# SCH_Embedded_Watch_2023-10-27.net
KiCad netlist of a schematic drawn in EasyEDA
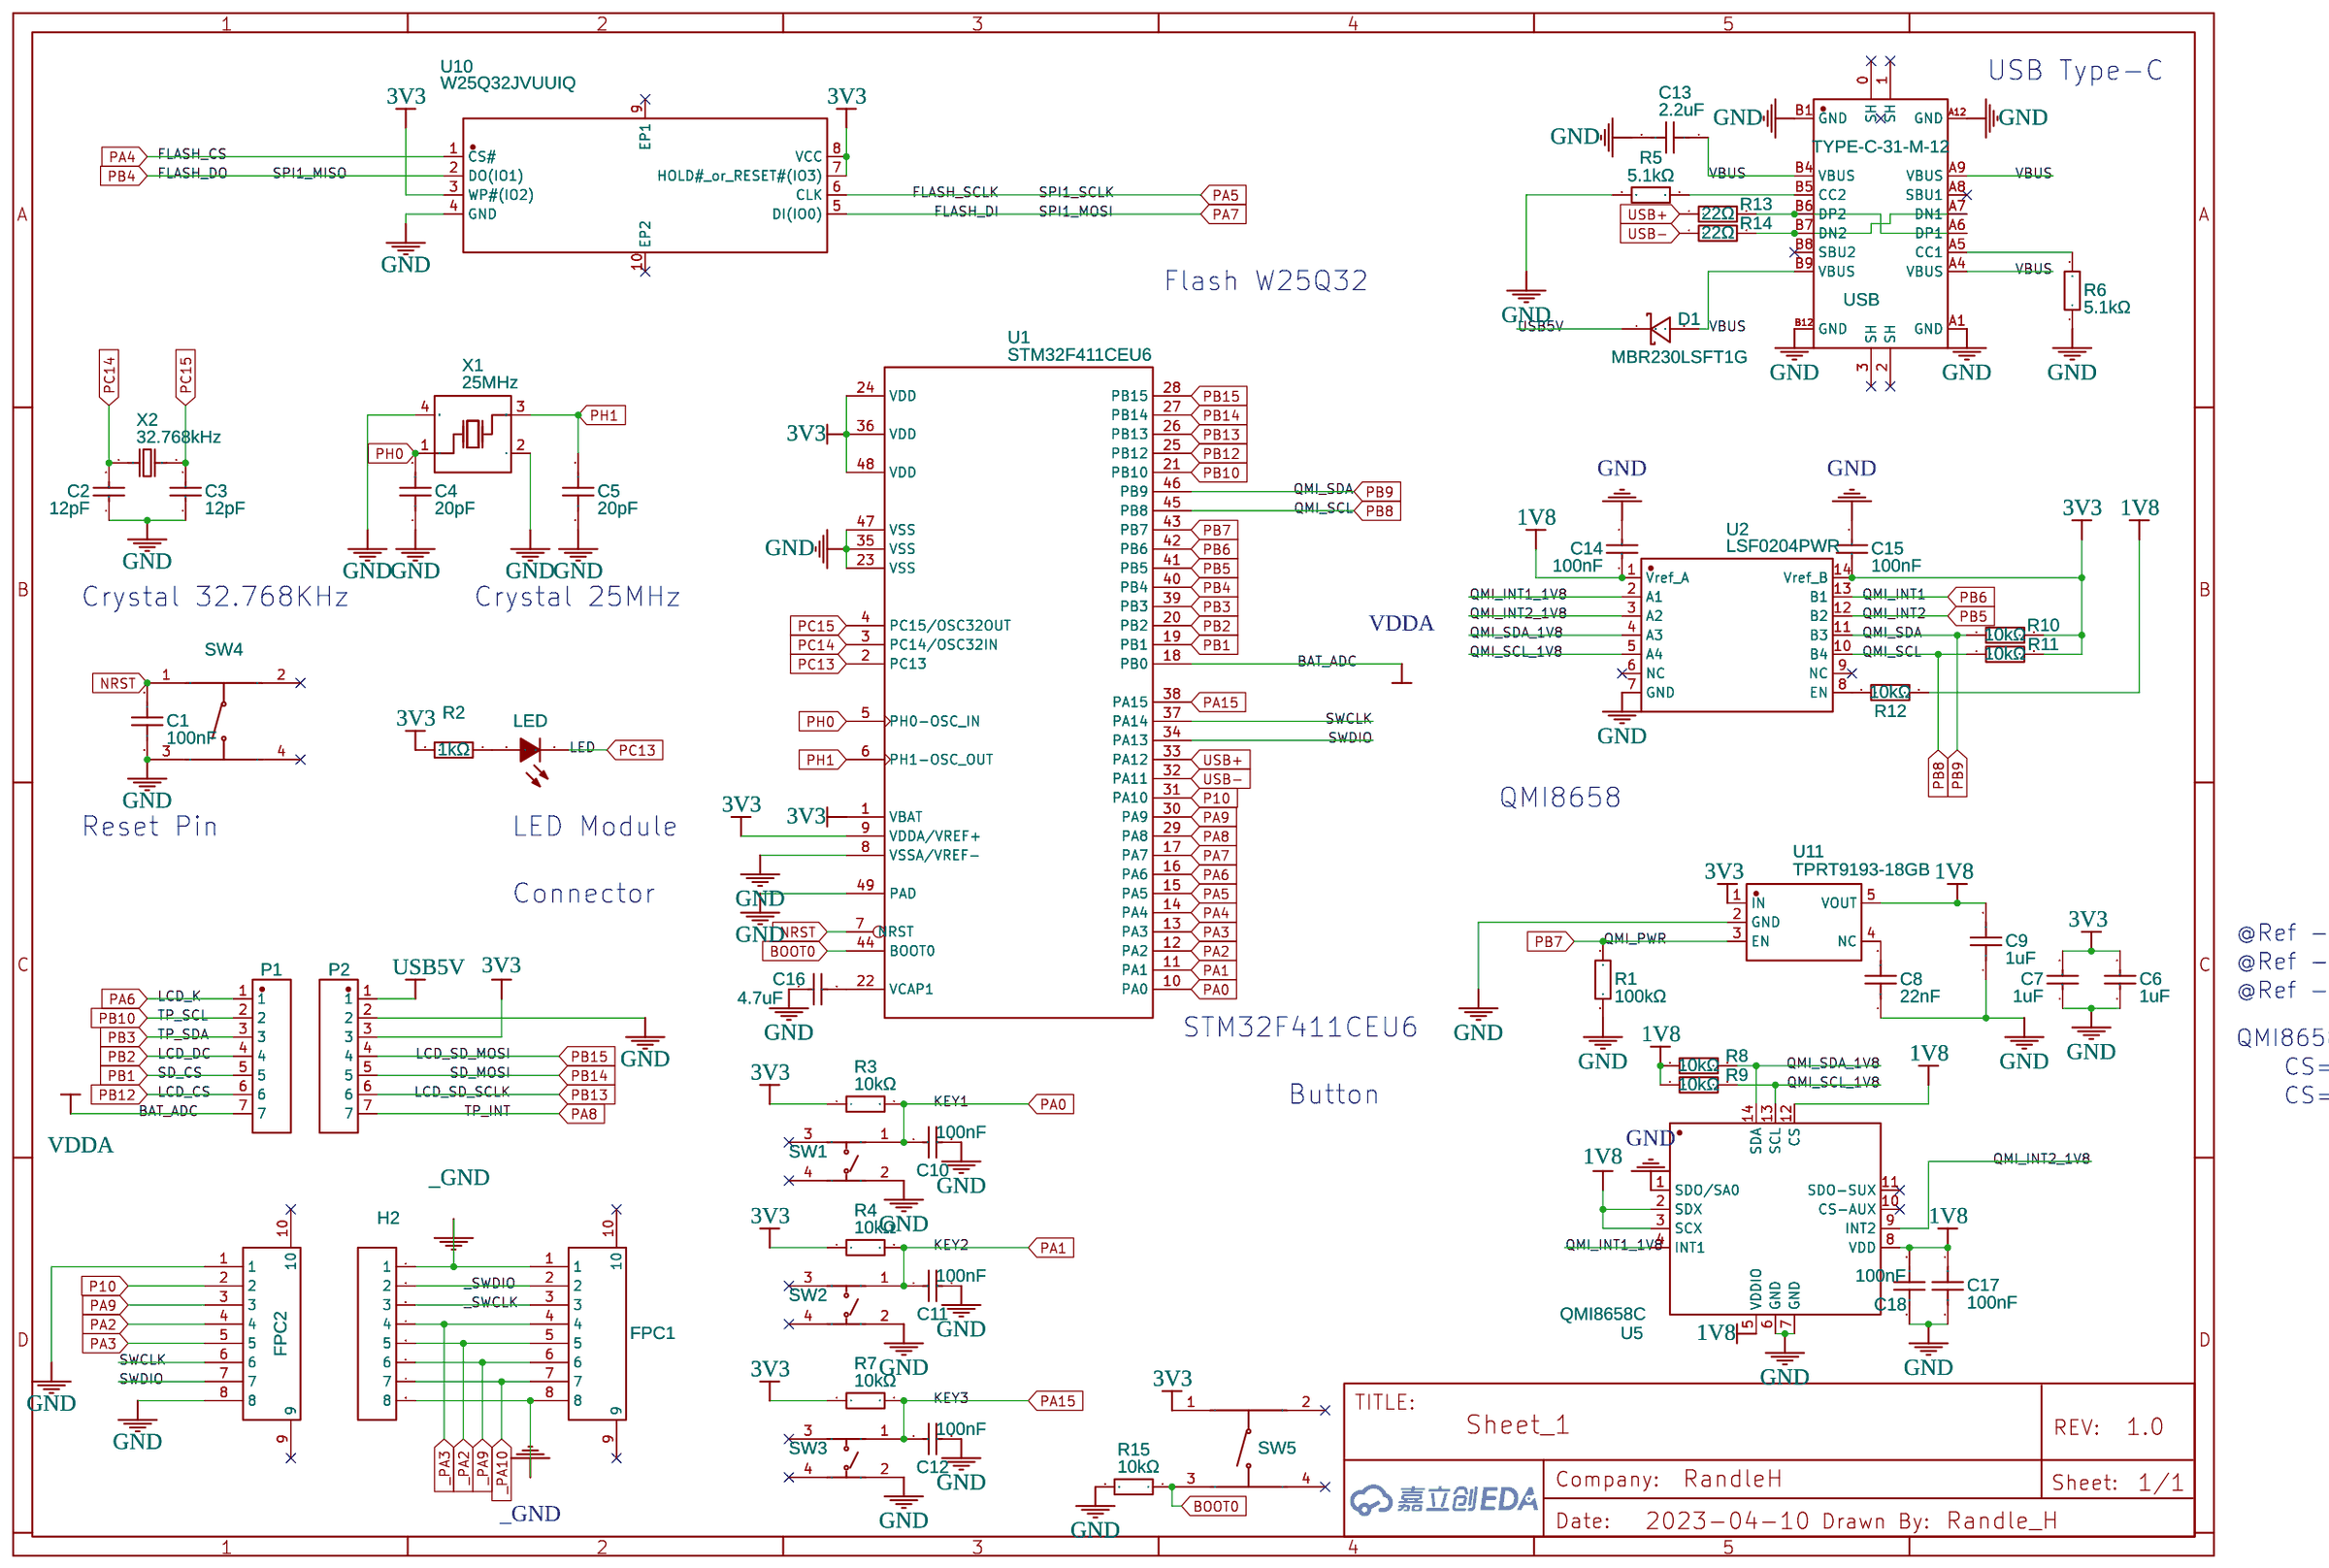
[diagram p0: schematic sheet]

(export (version "E")
  (design (tool "Eeschema 10.0.6"))
  (components
    (comp (ref "C1")
      (value "100nF")
      (fields
        (field (name "Manufacturer Part") "CL05B104KB54PNC")
        (field (name "Manufacturer") "SAMSUNG(三星)")
      )
      (libsource (lib "") (part "CL05B104KB54PNC"))
    )
    (comp (ref "C2")
      (value "12pF")
      (fields
        (field (name "Manufacturer Part") "GRM0335C1H120GA01D")
        (field (name "Manufacturer") "muRata(村田)")
      )
      (libsource (lib "") (part "GRM0335C1H120GA01D"))
    )
    (comp (ref "C3")
      (value "12pF")
      (fields
        (field (name "Manufacturer Part") "GRM0335C1H120GA01D")
        (field (name "Manufacturer") "muRata(村田)")
      )
      (libsource (lib "") (part "GRM0335C1H120GA01D_1"))
    )
    (comp (ref "C4")
      (value "20pF")
      (fields
        (field (name "Manufacturer Part") "GRM0335C1H200GA01D")
        (field (name "Manufacturer") "muRata(村田)")
      )
      (libsource (lib "") (part "GRM0335C1H200GA01D"))
    )
    (comp (ref "C5")
      (value "20pF")
      (fields
        (field (name "Manufacturer Part") "GRM0335C1H200GA01D")
        (field (name "Manufacturer") "muRata(村田)")
      )
      (libsource (lib "") (part "GRM0335C1H200GA01D"))
    )
    (comp (ref "C6")
      (value "1uF")
      (fields
        (field (name "Manufacturer Part") "GRM033R61A105ME44D")
        (field (name "Manufacturer") "muRata(村田)")
      )
      (libsource (lib "") (part "GRM033R61A105ME44D"))
    )
    (comp (ref "C7")
      (value "1uF")
      (fields
        (field (name "Manufacturer Part") "GRM033R61A105ME44D")
        (field (name "Manufacturer") "muRata(村田)")
      )
      (libsource (lib "") (part "GRM033R61A105ME44D_1"))
    )
    (comp (ref "C8")
      (value "22nF")
      (fields (field (name "Manufacturer Part") "0201X223K160NT") (field (name "Manufacturer") "FH(风华)"))
      (libsource (lib "") (part "0201X223K160NT"))
    )
    (comp (ref "C9")
      (value "1uF")
      (fields
        (field (name "Manufacturer Part") "JMK063ABJ105MP-F")
        (field (name "Manufacturer") "TAIYO YUDEN(太诱)")
      )
      (libsource (lib "") (part "JMK063ABJ105MP-F"))
    )
    (comp (ref "C10")
      (value "100nF")
      (fields
        (field (name "Manufacturer Part") "CL05B104KO5NNNC")
        (field (name "Manufacturer") "SAMSUNG(三星)")
      )
      (libsource (lib "") (part "CL05B104KO5NNNC"))
    )
    (comp (ref "C11")
      (value "100nF")
      (fields
        (field (name "Manufacturer Part") "CL05B104KO5NNNC")
        (field (name "Manufacturer") "SAMSUNG(三星)")
      )
      (libsource (lib "") (part "CL05B104KO5NNNC"))
    )
    (comp (ref "C12")
      (value "100nF")
      (fields
        (field (name "Manufacturer Part") "CL05B104KO5NNNC")
        (field (name "Manufacturer") "SAMSUNG(三星)")
      )
      (libsource (lib "") (part "CL05B104KO5NNNC"))
    )
    (comp (ref "C13")
      (value "2.2uF")
      (fields
        (field (name "Manufacturer Part") "CL21A225KBQNNNE")
        (field (name "Manufacturer") "SAMSUNG(三星)")
      )
      (libsource (lib "") (part "CL21A225KBQNNNE"))
    )
    (comp (ref "C14")
      (value "100nF")
      (fields
        (field (name "Manufacturer Part") "CL05B104KO5NNNC")
        (field (name "Manufacturer") "SAMSUNG(三星)")
      )
      (libsource (lib "") (part "CL05B104KO5NNNC_1"))
    )
    (comp (ref "C15")
      (value "100nF")
      (fields
        (field (name "Manufacturer Part") "CL05B104KO5NNNC")
        (field (name "Manufacturer") "SAMSUNG(三星)")
      )
      (libsource (lib "") (part "CL05B104KO5NNNC_2"))
    )
    (comp (ref "C16")
      (value "4.7uF")
      (fields
        (field (name "Manufacturer Part") "CL05A475MP5NRNC")
        (field (name "Manufacturer") "SAMSUNG(三星)")
      )
      (libsource (lib "") (part "CL05A475MP5NRNC"))
    )
    (comp (ref "C17")
      (value "100nF")
      (fields
        (field (name "Manufacturer Part") "CL03A104KQ3NNNC")
        (field (name "Manufacturer") "SAMSUNG(三星)")
      )
      (libsource (lib "") (part "CL03A104KQ3NNNC"))
    )
    (comp (ref "C18")
      (value "100nF")
      (fields
        (field (name "Manufacturer Part") "CL03A104KQ3NNNC")
        (field (name "Manufacturer") "SAMSUNG(三星)")
      )
      (libsource (lib "") (part "CL03A104KQ3NNNC"))
    )
    (comp (ref "D1")
      (value "MBR230LSFT1G")
      (fields (field (name "Manufacturer") "onsemi(安森美)"))
      (libsource (lib "") (part "MBR230LSFT1G"))
    )
    (comp (ref "FPC1")
      (value "AFC01-S08FCA-00")
      (fields (field (name "Manufacturer") "JS(钜硕电子)"))
      (libsource (lib "") (part "AFC01-S08FCA-00"))
    )
    (comp (ref "FPC2")
      (value "AFC01-S08FCA-00")
      (fields (field (name "Manufacturer") "JS(钜硕电子)"))
      (libsource (lib "") (part "AFC01-S08FCA-00"))
    )
    (comp (ref "H2") (value "HDR-F-2.54_1x8") (libsource (lib "") (part "HDR-F-2.54_1x8")))
    (comp (ref "LED")
      (value "19-213/Y2C-CQ2R2L/3T(CY)")
      (fields (field (name "Manufacturer") "EVERLIGHT(亿光)"))
      (libsource (lib "") (part "19-213/Y2C-CQ2R2L/3T(CY)"))
    )
    (comp (ref "P1")
      (value "PM2.54-1*7")
      (fields
        (field (name "Manufacturer Part") "X6511WVS-07H-C60D48R1")
        (field (name "Manufacturer") "XKB Connectivity(中国星坤)")
      )
      (libsource (lib "") (part "PM2.54-1*7"))
    )
    (comp (ref "P2")
      (value "PM2.54-1*7")
      (fields
        (field (name "Manufacturer Part") "X6511WVS-07H-C60D48R1")
        (field (name "Manufacturer") "XKB Connectivity(中国星坤)")
      )
      (libsource (lib "") (part "PM2.54-1*7_1"))
    )
    (comp (ref "R1")
      (value "100kΩ")
      (fields
        (field (name "Manufacturer Part") "0402WGF1003TCE")
        (field (name "Manufacturer") "UNI-ROYAL(厚声)")
      )
      (libsource (lib "") (part "0402WGF1003TCE"))
    )
    (comp (ref "R2")
      (value "1kΩ")
      (fields
        (field (name "Manufacturer Part") "0402WGF1001TCE")
        (field (name "Manufacturer") "UNI-ROYAL(厚声)")
      )
      (libsource (lib "") (part "0402WGF1001TCE"))
    )
    (comp (ref "R3")
      (value "10kΩ")
      (fields
        (field (name "Manufacturer Part") "0402WGF1002TCE")
        (field (name "Manufacturer") "UNI-ROYAL(厚声)")
      )
      (libsource (lib "") (part "0402WGF1002TCE"))
    )
    (comp (ref "R4")
      (value "10kΩ")
      (fields
        (field (name "Manufacturer Part") "0402WGF1002TCE")
        (field (name "Manufacturer") "UNI-ROYAL(厚声)")
      )
      (libsource (lib "") (part "0402WGF1002TCE"))
    )
    (comp (ref "R5")
      (value "5.1kΩ")
      (fields
        (field (name "Manufacturer Part") "0402WGF5101TCE")
        (field (name "Manufacturer") "UNI-ROYAL(厚声)")
      )
      (libsource (lib "") (part "0402WGF5101TCE_1"))
    )
    (comp (ref "R6")
      (value "5.1kΩ")
      (fields
        (field (name "Manufacturer Part") "0402WGF5101TCE")
        (field (name "Manufacturer") "UNI-ROYAL(厚声)")
      )
      (libsource (lib "") (part "0402WGF5101TCE"))
    )
    (comp (ref "R7")
      (value "10kΩ")
      (fields
        (field (name "Manufacturer Part") "0402WGF1002TCE")
        (field (name "Manufacturer") "UNI-ROYAL(厚声)")
      )
      (libsource (lib "") (part "0402WGF1002TCE"))
    )
    (comp (ref "R8")
      (value "10kΩ")
      (fields (field (name "Manufacturer Part") "RC0201JR-0710KL") (field (name "Manufacturer") "YAGEO(国巨)"))
      (libsource (lib "") (part "RC0201JR-0710KL"))
    )
    (comp (ref "R9")
      (value "10kΩ")
      (fields (field (name "Manufacturer Part") "RC0201JR-0710KL") (field (name "Manufacturer") "YAGEO(国巨)"))
      (libsource (lib "") (part "RC0201JR-0710KL"))
    )
    (comp (ref "R10")
      (value "10kΩ")
      (fields
        (field (name "Manufacturer Part") "0402WGF1002TCE")
        (field (name "Manufacturer") "UNI-ROYAL(厚声)")
      )
      (libsource (lib "") (part "0402WGF1002TCE"))
    )
    (comp (ref "R11")
      (value "10kΩ")
      (fields
        (field (name "Manufacturer Part") "0402WGF1002TCE")
        (field (name "Manufacturer") "UNI-ROYAL(厚声)")
      )
      (libsource (lib "") (part "0402WGF1002TCE"))
    )
    (comp (ref "R12")
      (value "10kΩ")
      (fields
        (field (name "Manufacturer Part") "0402WGF1002TCE")
        (field (name "Manufacturer") "UNI-ROYAL(厚声)")
      )
      (libsource (lib "") (part "0402WGF1002TCE"))
    )
    (comp (ref "R13")
      (value "22Ω")
      (fields
        (field (name "Manufacturer Part") "0402WGF220JTCE")
        (field (name "Manufacturer") "UNI-ROYAL(厚声)")
      )
      (libsource (lib "") (part "0402WGF220JTCE"))
    )
    (comp (ref "R14")
      (value "22Ω")
      (fields
        (field (name "Manufacturer Part") "0402WGF220JTCE")
        (field (name "Manufacturer") "UNI-ROYAL(厚声)")
      )
      (libsource (lib "") (part "0402WGF220JTCE"))
    )
    (comp (ref "R15")
      (value "10kΩ")
      (fields
        (field (name "Manufacturer Part") "0402WGF1002TCE")
        (field (name "Manufacturer") "UNI-ROYAL(厚声)")
      )
      (libsource (lib "") (part "0402WGF1002TCE_1"))
    )
    (comp (ref "SW1")
      (value "EVQPUD02K")
      (fields (field (name "Manufacturer") "PANASONIC(松下)"))
      (libsource (lib "") (part "EVQPUD02K"))
    )
    (comp (ref "SW2")
      (value "EVQPUD02K")
      (fields (field (name "Manufacturer") "PANASONIC(松下)"))
      (libsource (lib "") (part "EVQPUD02K"))
    )
    (comp (ref "SW3")
      (value "EVQPUD02K")
      (fields (field (name "Manufacturer") "PANASONIC(松下)"))
      (libsource (lib "") (part "EVQPUD02K"))
    )
    (comp (ref "SW4")
      (value "PTS830GM140SMTRLFS")
      (fields (field (name "Manufacturer") "C&K"))
      (libsource (lib "") (part "PTS830GM140SMTRLFS"))
    )
    (comp (ref "SW5")
      (value "PTS830GM140SMTRLFS")
      (fields (field (name "Manufacturer") "C&K"))
      (libsource (lib "") (part "PTS830GM140SMTRLFS"))
    )
    (comp (ref "U1")
      (value "STM32F411CEU6")
      (fields (field (name "Manufacturer") "ST(意法半导体)"))
      (libsource (lib "") (part "STM32F411CEU6"))
    )
    (comp (ref "U2")
      (value "LSF0204PWR")
      (fields (field (name "Manufacturer") "TI(德州仪器)"))
      (libsource (lib "") (part "LSF0204PWR"))
    )
    (comp (ref "U5")
      (value "QMI8658C")
      (fields (field (name "Manufacturer") "QST(上海矽睿)"))
      (libsource (lib "") (part "QMI8658C"))
    )
    (comp (ref "U10")
      (value "W25Q32JVUUIQ")
      (fields (field (name "Manufacturer") "WINBOND(华邦)"))
      (libsource (lib "") (part "W25Q32JVUUIQ"))
    )
    (comp (ref "U11")
      (value "TPRT9193-18GB")
      (fields (field (name "Manufacturer") "TECH PUBLIC(台舟)"))
      (libsource (lib "") (part "TPRT9193-18GB"))
    )
    (comp (ref "USB")
      (value "TYPE-C-31-M-12")
      (fields (field (name "Manufacturer") "韩国韩荣"))
      (libsource (lib "") (part "TYPE-C-31-M-12"))
    )
    (comp (ref "X1")
      (value "25MHz")
      (fields (field (name "Manufacturer Part") "TAXM25M4RLBCCT2T") (field (name "Manufacturer") "TAE(雅晶鑫)"))
      (libsource (lib "") (part "SMD-3225_4P25MHZ20PF10PPM-40&#126;+85℃"))
    )
    (comp (ref "X2")
      (value "32.768kHz")
      (fields (field (name "Manufacturer Part") "Q13FC1350000400") (field (name "Manufacturer") "EPSON(爱普生)"))
      (libsource (lib "") (part "Q13FC1350000400"))
    )
  )
  (nets
    (net (code "1") (name "/QMI_INT1_1V8") (class "Default")
      (node (ref "U2") (pin "2") (pinfunction "A1_2") (pintype "unspecified"))
      (node (ref "U5") (pin "4") (pinfunction "INT1_4") (pintype "unspecified"))
    )
    (net (code "2") (name "/QMI_INT2_1V8") (class "Default")
      (node (ref "U2") (pin "3") (pinfunction "A2_3") (pintype "unspecified"))
      (node (ref "U5") (pin "9") (pinfunction "INT2_9") (pintype "unspecified"))
    )
    (net (code "3") (name "/QMI_SCL_1V8") (class "Default")
      (node (ref "R9") (pin "2") (pinfunction "2_2") (pintype "input"))
      (node (ref "U2") (pin "5") (pinfunction "A4_5") (pintype "unspecified"))
      (node (ref "U5") (pin "13") (pinfunction "SCL_13") (pintype "unspecified"))
    )
    (net (code "4") (name "/QMI_SDA_1V8") (class "Default")
      (node (ref "R8") (pin "2") (pinfunction "2_2") (pintype "input"))
      (node (ref "U2") (pin "4") (pinfunction "A3_4") (pintype "unspecified"))
      (node (ref "U5") (pin "14") (pinfunction "SDA_14") (pintype "unspecified"))
    )
    (net (code "5") (name "/SWCLK") (class "Default")
      (node (ref "FPC2") (pin "6") (pinfunction "6_6") (pintype "unspecified"))
      (node (ref "U1") (pin "37") (pinfunction "PA14_37") (pintype "unspecified"))
    )
    (net (code "6") (name "/SWDIO") (class "Default")
      (node (ref "FPC2") (pin "7") (pinfunction "7_7") (pintype "unspecified"))
      (node (ref "U1") (pin "34") (pinfunction "PA13_34") (pintype "unspecified"))
    )
    (net (code "7") (name "/VBUS") (class "Default")
      (node (ref "C13") (pin "1") (pinfunction "1_1") (pintype "unspecified"))
      (node (ref "D1") (pin "2") (pinfunction "A_2") (pintype "unspecified"))
      (node (ref "USB") (pin "A4") (pinfunction "VBUS_A4") (pintype "unspecified"))
      (node (ref "USB") (pin "A9") (pinfunction "VBUS_A9") (pintype "unspecified"))
      (node (ref "USB") (pin "B4") (pinfunction "VBUS_B4") (pintype "unspecified"))
      (node (ref "USB") (pin "B9") (pinfunction "VBUS_B9") (pintype "unspecified"))
    )
    (net (code "8") (name "/_SWCLK") (class "Default")
      (node (ref "FPC1") (pin "3") (pinfunction "3_3") (pintype "unspecified"))
      (node (ref "H2") (pin "3") (pinfunction "3_3") (pintype "unspecified"))
    )
    (net (code "9") (name "/_SWDIO") (class "Default")
      (node (ref "FPC1") (pin "2") (pinfunction "2_2") (pintype "unspecified"))
      (node (ref "H2") (pin "2") (pinfunction "2_2") (pintype "unspecified"))
    )
    (net (code "10") (name "1V8") (class "Default")
      (node (ref "C14") (pin "1") (pinfunction "1_1") (pintype "input"))
      (node (ref "C17") (pin "1") (pinfunction "1_1") (pintype "unspecified"))
      (node (ref "C18") (pin "1") (pinfunction "1_1") (pintype "unspecified"))
      (node (ref "C9") (pin "2") (pinfunction "2_2") (pintype "unspecified"))
      (node (ref "R12") (pin "2") (pinfunction "2_2") (pintype "input"))
      (node (ref "R8") (pin "1") (pinfunction "1_1") (pintype "input"))
      (node (ref "R9") (pin "1") (pinfunction "1_1") (pintype "input"))
      (node (ref "U11") (pin "5") (pinfunction "VOUT_5") (pintype "unspecified"))
      (node (ref "U2") (pin "1") (pinfunction "Vref_A_1") (pintype "unspecified"))
      (node (ref "U5") (pin "12") (pinfunction "CS_12") (pintype "unspecified"))
      (node (ref "U5") (pin "2") (pinfunction "SDX_2") (pintype "unspecified"))
      (node (ref "U5") (pin "3") (pinfunction "SCX_3") (pintype "unspecified"))
      (node (ref "U5") (pin "5") (pinfunction "VDDIO_5") (pintype "unspecified"))
      (node (ref "U5") (pin "8") (pinfunction "VDD_8") (pintype "unspecified"))
    )
    (net (code "11") (name "3V3") (class "Default")
      (node (ref "C15") (pin "1") (pinfunction "1_1") (pintype "input"))
      (node (ref "C6") (pin "2") (pinfunction "2_2") (pintype "input"))
      (node (ref "C7") (pin "2") (pinfunction "2_2") (pintype "input"))
      (node (ref "P2") (pin "3") (pinfunction "3_3") (pintype "unspecified"))
      (node (ref "R10") (pin "2") (pinfunction "2_2") (pintype "input"))
      (node (ref "R11") (pin "2") (pinfunction "2_2") (pintype "input"))
      (node (ref "R2") (pin "1") (pinfunction "1_1") (pintype "input"))
      (node (ref "R3") (pin "1") (pinfunction "1_1") (pintype "input"))
      (node (ref "R4") (pin "1") (pinfunction "1_1") (pintype "input"))
      (node (ref "R7") (pin "1") (pinfunction "1_1") (pintype "input"))
      (node (ref "SW5") (pin "1") (pinfunction "1_1") (pintype "unspecified"))
      (node (ref "U1") (pin "1") (pinfunction "VBAT_1") (pintype "passive"))
      (node (ref "U1") (pin "24") (pinfunction "VDD_24") (pintype "unspecified"))
      (node (ref "U1") (pin "36") (pinfunction "VDD_36") (pintype "unspecified"))
      (node (ref "U1") (pin "48") (pinfunction "VDD_48") (pintype "unspecified"))
      (node (ref "U1") (pin "9") (pinfunction "VDDA/VREF+_9") (pintype "passive"))
      (node (ref "U10") (pin "3") (pinfunction "WP#(IO2)_3") (pintype "unspecified"))
      (node (ref "U10") (pin "7") (pinfunction "HOLD#_or_RESET#(IO3)_7") (pintype "unspecified"))
      (node (ref "U10") (pin "8") (pinfunction "VCC_8") (pintype "unspecified"))
      (node (ref "U11") (pin "1") (pinfunction "IN_1") (pintype "unspecified"))
      (node (ref "U2") (pin "14") (pinfunction "Vref_B_14") (pintype "unspecified"))
    )
    (net (code "12") (name "BOOT0") (class "Default")
      (node (ref "R15") (pin "1") (pinfunction "1_1") (pintype "input"))
      (node (ref "SW5") (pin "3") (pinfunction "3_3") (pintype "unspecified"))
      (node (ref "U1") (pin "44") (pinfunction "BOOT0_44") (pintype "input"))
    )
    (net (code "13") (name "GND") (class "Default")
      (node (ref "C1") (pin "1") (pinfunction "1_1") (pintype "unspecified"))
      (node (ref "C10") (pin "2") (pinfunction "2_2") (pintype "input"))
      (node (ref "C11") (pin "2") (pinfunction "2_2") (pintype "input"))
      (node (ref "C12") (pin "2") (pinfunction "2_2") (pintype "input"))
      (node (ref "C13") (pin "2") (pinfunction "2_2") (pintype "unspecified"))
      (node (ref "C14") (pin "2") (pinfunction "2_2") (pintype "input"))
      (node (ref "C15") (pin "2") (pinfunction "2_2") (pintype "input"))
      (node (ref "C16") (pin "1") (pinfunction "1_1") (pintype "input"))
      (node (ref "C17") (pin "2") (pinfunction "2_2") (pintype "unspecified"))
      (node (ref "C18") (pin "2") (pinfunction "2_2") (pintype "unspecified"))
      (node (ref "C2") (pin "1") (pinfunction "1_1") (pintype "input"))
      (node (ref "C3") (pin "1") (pinfunction "1_1") (pintype "input"))
      (node (ref "C4") (pin "1") (pinfunction "1_1") (pintype "unspecified"))
      (node (ref "C5") (pin "1") (pinfunction "1_1") (pintype "unspecified"))
      (node (ref "C6") (pin "1") (pinfunction "1_1") (pintype "input"))
      (node (ref "C7") (pin "1") (pinfunction "1_1") (pintype "input"))
      (node (ref "C8") (pin "1") (pinfunction "1_1") (pintype "unspecified"))
      (node (ref "C9") (pin "1") (pinfunction "1_1") (pintype "unspecified"))
      (node (ref "FPC2") (pin "1") (pinfunction "1_1") (pintype "unspecified"))
      (node (ref "FPC2") (pin "8") (pinfunction "8_8") (pintype "unspecified"))
      (node (ref "P2") (pin "2") (pinfunction "2_2") (pintype "unspecified"))
      (node (ref "R1") (pin "1") (pinfunction "1_1") (pintype "input"))
      (node (ref "R15") (pin "2") (pinfunction "2_2") (pintype "input"))
      (node (ref "R5") (pin "2") (pinfunction "2_2") (pintype "input"))
      (node (ref "R6") (pin "1") (pinfunction "1_1") (pintype "input"))
      (node (ref "SW1") (pin "2") (pinfunction "2_2") (pintype "unspecified"))
      (node (ref "SW2") (pin "2") (pinfunction "2_2") (pintype "unspecified"))
      (node (ref "SW3") (pin "2") (pinfunction "2_2") (pintype "unspecified"))
      (node (ref "SW4") (pin "3") (pinfunction "3_3") (pintype "unspecified"))
      (node (ref "U1") (pin "23") (pinfunction "VSS_23") (pintype "unspecified"))
      (node (ref "U1") (pin "35") (pinfunction "VSS_35") (pintype "unspecified"))
      (node (ref "U1") (pin "47") (pinfunction "VSS_47") (pintype "unspecified"))
      (node (ref "U1") (pin "49") (pinfunction "PAD_49") (pintype "passive"))
      (node (ref "U1") (pin "8") (pinfunction "VSSA/VREF-_8") (pintype "passive"))
      (node (ref "U10") (pin "4") (pinfunction "GND_4") (pintype "unspecified"))
      (node (ref "U11") (pin "2") (pinfunction "GND_2") (pintype "unspecified"))
      (node (ref "U2") (pin "7") (pinfunction "GND_7") (pintype "unspecified"))
      (node (ref "U5") (pin "1") (pinfunction "SDO/SA0_1") (pintype "unspecified"))
      (node (ref "U5") (pin "6") (pinfunction "GND_6") (pintype "unspecified"))
      (node (ref "U5") (pin "7") (pinfunction "GND_7") (pintype "unspecified"))
      (node (ref "USB") (pin "A1") (pinfunction "GND_A1") (pintype "unspecified"))
      (node (ref "USB") (pin "A12") (pinfunction "GND_A12") (pintype "unspecified"))
      (node (ref "USB") (pin "B1") (pinfunction "GND_B1") (pintype "unspecified"))
      (node (ref "USB") (pin "B12") (pinfunction "GND_B12") (pintype "unspecified"))
      (node (ref "X1") (pin "2") (pinfunction "GND_2") (pintype "unspecified"))
      (node (ref "X1") (pin "4") (pinfunction "GND_4") (pintype "unspecified"))
    )
    (net (code "14") (name "NRST") (class "Default")
      (node (ref "C1") (pin "2") (pinfunction "2_2") (pintype "unspecified"))
      (node (ref "SW4") (pin "1") (pinfunction "1_1") (pintype "unspecified"))
      (node (ref "U1") (pin "7") (pinfunction "NRST_7") (pintype "unspecified"))
    )
    (net (code "15") (name "Net-(LED-A)") (class "Default")
      (node (ref "LED") (pin "2") (pinfunction "A_2") (pintype "input"))
      (node (ref "R2") (pin "2") (pinfunction "2_2") (pintype "input"))
    )
    (net (code "16") (name "Net-(U1-VCAP1)") (class "Default")
      (node (ref "C16") (pin "2") (pinfunction "2_2") (pintype "input"))
      (node (ref "U1") (pin "22") (pinfunction "VCAP1_22") (pintype "passive"))
    )
    (net (code "17") (name "Net-(U2-EN)") (class "Default")
      (node (ref "R12") (pin "1") (pinfunction "1_1") (pintype "input"))
      (node (ref "U2") (pin "8") (pinfunction "EN_8") (pintype "unspecified"))
    )
    (net (code "18") (name "Net-(U11-NC)") (class "Default")
      (node (ref "C8") (pin "2") (pinfunction "2_2") (pintype "unspecified"))
      (node (ref "U11") (pin "4") (pinfunction "NC_4") (pintype "unspecified"))
    )
    (net (code "19") (name "Net-(USB-CC1)") (class "Default")
      (node (ref "R6") (pin "2") (pinfunction "2_2") (pintype "input"))
      (node (ref "USB") (pin "A5") (pinfunction "CC1_A5") (pintype "unspecified"))
    )
    (net (code "20") (name "Net-(USB-CC2)") (class "Default")
      (node (ref "R5") (pin "1") (pinfunction "1_1") (pintype "input"))
      (node (ref "USB") (pin "B5") (pinfunction "CC2_B5") (pintype "unspecified"))
    )
    (net (code "21") (name "Net-(USB-DN1)") (class "Default")
      (node (ref "R14") (pin "2") (pinfunction "2_2") (pintype "input"))
      (node (ref "USB") (pin "A7") (pinfunction "DN1_A7") (pintype "unspecified"))
      (node (ref "USB") (pin "B7") (pinfunction "DN2_B7") (pintype "unspecified"))
    )
    (net (code "22") (name "Net-(USB-DP1)") (class "Default")
      (node (ref "R13") (pin "2") (pinfunction "2_2") (pintype "input"))
      (node (ref "USB") (pin "A6") (pinfunction "DP1_A6") (pintype "unspecified"))
      (node (ref "USB") (pin "B6") (pinfunction "DP2_B6") (pintype "unspecified"))
    )
    (net (code "23") (name "P10") (class "Default")
      (node (ref "FPC2") (pin "2") (pinfunction "2_2") (pintype "unspecified"))
      (node (ref "U1") (pin "31") (pinfunction "PA10_31") (pintype "unspecified"))
    )
    (net (code "24") (name "PA0") (class "Default")
      (node (ref "C10") (pin "1") (pinfunction "1_1") (pintype "input"))
      (node (ref "R3") (pin "2") (pinfunction "2_2") (pintype "input"))
      (node (ref "SW1") (pin "1") (pinfunction "1_1") (pintype "unspecified"))
      (node (ref "U1") (pin "10") (pinfunction "PA0_10") (pintype "unspecified"))
    )
    (net (code "25") (name "PA1") (class "Default")
      (node (ref "C11") (pin "1") (pinfunction "1_1") (pintype "input"))
      (node (ref "R4") (pin "2") (pinfunction "2_2") (pintype "input"))
      (node (ref "SW2") (pin "1") (pinfunction "1_1") (pintype "unspecified"))
      (node (ref "U1") (pin "11") (pinfunction "PA1_11") (pintype "unspecified"))
    )
    (net (code "26") (name "PA2") (class "Default")
      (node (ref "FPC2") (pin "4") (pinfunction "4_4") (pintype "unspecified"))
      (node (ref "U1") (pin "12") (pinfunction "PA2_12") (pintype "unspecified"))
    )
    (net (code "27") (name "PA3") (class "Default")
      (node (ref "FPC2") (pin "5") (pinfunction "5_5") (pintype "unspecified"))
      (node (ref "U1") (pin "13") (pinfunction "PA3_13") (pintype "unspecified"))
    )
    (net (code "28") (name "PA4") (class "Default")
      (node (ref "U1") (pin "14") (pinfunction "PA4_14") (pintype "unspecified"))
      (node (ref "U10") (pin "1") (pinfunction "CS#_1") (pintype "unspecified"))
    )
    (net (code "29") (name "PA5") (class "Default")
      (node (ref "U1") (pin "15") (pinfunction "PA5_15") (pintype "unspecified"))
      (node (ref "U10") (pin "6") (pinfunction "CLK_6") (pintype "unspecified"))
    )
    (net (code "30") (name "PA6") (class "Default")
      (node (ref "P1") (pin "1") (pinfunction "1_1") (pintype "unspecified"))
      (node (ref "U1") (pin "16") (pinfunction "PA6_16") (pintype "unspecified"))
    )
    (net (code "31") (name "PA7") (class "Default")
      (node (ref "U1") (pin "17") (pinfunction "PA7_17") (pintype "unspecified"))
      (node (ref "U10") (pin "5") (pinfunction "DI(IO0)_5") (pintype "unspecified"))
    )
    (net (code "32") (name "PA8") (class "Default")
      (node (ref "P2") (pin "7") (pinfunction "7_7") (pintype "unspecified"))
      (node (ref "U1") (pin "29") (pinfunction "PA8_29") (pintype "unspecified"))
    )
    (net (code "33") (name "PA9") (class "Default")
      (node (ref "FPC2") (pin "3") (pinfunction "3_3") (pintype "unspecified"))
      (node (ref "U1") (pin "30") (pinfunction "PA9_30") (pintype "unspecified"))
    )
    (net (code "34") (name "PA15") (class "Default")
      (node (ref "C12") (pin "1") (pinfunction "1_1") (pintype "input"))
      (node (ref "R7") (pin "2") (pinfunction "2_2") (pintype "input"))
      (node (ref "SW3") (pin "1") (pinfunction "1_1") (pintype "unspecified"))
      (node (ref "U1") (pin "38") (pinfunction "PA15_38") (pintype "unspecified"))
    )
    (net (code "35") (name "PB1") (class "Default")
      (node (ref "P1") (pin "5") (pinfunction "5_5") (pintype "unspecified"))
      (node (ref "U1") (pin "19") (pinfunction "PB1_19") (pintype "unspecified"))
    )
    (net (code "36") (name "PB2") (class "Default")
      (node (ref "P1") (pin "4") (pinfunction "4_4") (pintype "unspecified"))
      (node (ref "U1") (pin "20") (pinfunction "PB2_20") (pintype "unspecified"))
    )
    (net (code "37") (name "PB3") (class "Default")
      (node (ref "P1") (pin "3") (pinfunction "3_3") (pintype "unspecified"))
      (node (ref "U1") (pin "39") (pinfunction "PB3_39") (pintype "unspecified"))
    )
    (net (code "38") (name "PB4") (class "Default")
      (node (ref "U1") (pin "40") (pinfunction "PB4_40") (pintype "unspecified"))
      (node (ref "U10") (pin "2") (pinfunction "DO(IO1)_2") (pintype "unspecified"))
    )
    (net (code "39") (name "PB5") (class "Default")
      (node (ref "U1") (pin "41") (pinfunction "PB5_41") (pintype "unspecified"))
      (node (ref "U2") (pin "12") (pinfunction "B2_12") (pintype "unspecified"))
    )
    (net (code "40") (name "PB6") (class "Default")
      (node (ref "U1") (pin "42") (pinfunction "PB6_42") (pintype "unspecified"))
      (node (ref "U2") (pin "13") (pinfunction "B1_13") (pintype "unspecified"))
    )
    (net (code "41") (name "PB7") (class "Default")
      (node (ref "R1") (pin "2") (pinfunction "2_2") (pintype "input"))
      (node (ref "U1") (pin "43") (pinfunction "PB7_43") (pintype "unspecified"))
      (node (ref "U11") (pin "3") (pinfunction "EN_3") (pintype "unspecified"))
    )
    (net (code "42") (name "PB8") (class "Default")
      (node (ref "R11") (pin "1") (pinfunction "1_1") (pintype "input"))
      (node (ref "U1") (pin "45") (pinfunction "PB8_45") (pintype "unspecified"))
      (node (ref "U2") (pin "10") (pinfunction "B4_10") (pintype "unspecified"))
    )
    (net (code "43") (name "PB9") (class "Default")
      (node (ref "R10") (pin "1") (pinfunction "1_1") (pintype "input"))
      (node (ref "U1") (pin "46") (pinfunction "PB9_46") (pintype "unspecified"))
      (node (ref "U2") (pin "11") (pinfunction "B3_11") (pintype "unspecified"))
    )
    (net (code "44") (name "PB10") (class "Default")
      (node (ref "P1") (pin "2") (pinfunction "2_2") (pintype "unspecified"))
      (node (ref "U1") (pin "21") (pinfunction "PB10_21") (pintype "unspecified"))
    )
    (net (code "45") (name "PB12") (class "Default")
      (node (ref "P1") (pin "6") (pinfunction "6_6") (pintype "unspecified"))
      (node (ref "U1") (pin "25") (pinfunction "PB12_25") (pintype "unspecified"))
    )
    (net (code "46") (name "PB13") (class "Default")
      (node (ref "P2") (pin "6") (pinfunction "6_6") (pintype "unspecified"))
      (node (ref "U1") (pin "26") (pinfunction "PB13_26") (pintype "unspecified"))
    )
    (net (code "47") (name "PB14") (class "Default")
      (node (ref "P2") (pin "5") (pinfunction "5_5") (pintype "unspecified"))
      (node (ref "U1") (pin "27") (pinfunction "PB14_27") (pintype "unspecified"))
    )
    (net (code "48") (name "PB15") (class "Default")
      (node (ref "P2") (pin "4") (pinfunction "4_4") (pintype "unspecified"))
      (node (ref "U1") (pin "28") (pinfunction "PB15_28") (pintype "unspecified"))
    )
    (net (code "49") (name "PC13") (class "Default")
      (node (ref "LED") (pin "1") (pinfunction "C_1") (pintype "input"))
      (node (ref "U1") (pin "2") (pinfunction "PC13_2") (pintype "unspecified"))
    )
    (net (code "50") (name "PC14") (class "Default")
      (node (ref "C2") (pin "2") (pinfunction "2_2") (pintype "input"))
      (node (ref "U1") (pin "3") (pinfunction "PC14/OSC32IN_3") (pintype "unspecified"))
      (node (ref "X2") (pin "1") (pinfunction "1_1") (pintype "unspecified"))
    )
    (net (code "51") (name "PC15") (class "Default")
      (node (ref "C3") (pin "2") (pinfunction "2_2") (pintype "input"))
      (node (ref "U1") (pin "4") (pinfunction "PC15/OSC32OUT_4") (pintype "unspecified"))
      (node (ref "X2") (pin "2") (pinfunction "2_2") (pintype "unspecified"))
    )
    (net (code "52") (name "PH0") (class "Default")
      (node (ref "C4") (pin "2") (pinfunction "2_2") (pintype "unspecified"))
      (node (ref "U1") (pin "5") (pinfunction "PH0-OSC_IN_5") (pintype "unspecified"))
      (node (ref "X1") (pin "1") (pinfunction "OSC1_1") (pintype "unspecified"))
    )
    (net (code "53") (name "PH1") (class "Default")
      (node (ref "C5") (pin "2") (pinfunction "2_2") (pintype "unspecified"))
      (node (ref "U1") (pin "6") (pinfunction "PH1-OSC_OUT_6") (pintype "unspecified"))
      (node (ref "X1") (pin "3") (pinfunction "OSC2_3") (pintype "unspecified"))
    )
    (net (code "54") (name "USB+") (class "Default")
      (node (ref "R13") (pin "1") (pinfunction "1_1") (pintype "input"))
      (node (ref "U1") (pin "33") (pinfunction "PA12_33") (pintype "unspecified"))
    )
    (net (code "55") (name "USB-") (class "Default")
      (node (ref "R14") (pin "1") (pinfunction "1_1") (pintype "input"))
      (node (ref "U1") (pin "32") (pinfunction "PA11_32") (pintype "unspecified"))
    )
    (net (code "56") (name "USB5V") (class "Default")
      (node (ref "D1") (pin "1") (pinfunction "C_1") (pintype "unspecified"))
      (node (ref "P2") (pin "1") (pinfunction "1_1") (pintype "unspecified"))
    )
    (net (code "57") (name "VDDA") (class "Default")
      (node (ref "P1") (pin "7") (pinfunction "7_7") (pintype "unspecified"))
      (node (ref "U1") (pin "18") (pinfunction "PB0_18") (pintype "unspecified"))
    )
    (net (code "58") (name "_GND") (class "Default")
      (node (ref "FPC1") (pin "1") (pinfunction "1_1") (pintype "unspecified"))
      (node (ref "FPC1") (pin "8") (pinfunction "8_8") (pintype "unspecified"))
      (node (ref "H2") (pin "1") (pinfunction "1_1") (pintype "unspecified"))
      (node (ref "H2") (pin "8") (pinfunction "8_8") (pintype "unspecified"))
    )
    (net (code "59") (name "_PA2") (class "Default")
      (node (ref "FPC1") (pin "5") (pinfunction "5_5") (pintype "unspecified"))
      (node (ref "H2") (pin "5") (pinfunction "5_5") (pintype "unspecified"))
    )
    (net (code "60") (name "_PA3") (class "Default")
      (node (ref "FPC1") (pin "4") (pinfunction "4_4") (pintype "unspecified"))
      (node (ref "H2") (pin "4") (pinfunction "4_4") (pintype "unspecified"))
    )
    (net (code "61") (name "_PA9") (class "Default")
      (node (ref "FPC1") (pin "6") (pinfunction "6_6") (pintype "unspecified"))
      (node (ref "H2") (pin "6") (pinfunction "6_6") (pintype "unspecified"))
    )
    (net (code "62") (name "_PA10") (class "Default")
      (node (ref "FPC1") (pin "7") (pinfunction "7_7") (pintype "unspecified"))
      (node (ref "H2") (pin "7") (pinfunction "7_7") (pintype "unspecified"))
    )
    (net (code "63") (name "unconnected-(FPC1-Pad9)") (class "Default")
      (node (ref "FPC1") (pin "9") (pinfunction "9_9") (pintype "unspecified+no_connect"))
    )
    (net (code "64") (name "unconnected-(FPC1-Pad10)") (class "Default")
      (node (ref "FPC1") (pin "10") (pinfunction "10_10") (pintype "unspecified+no_connect"))
    )
    (net (code "65") (name "unconnected-(FPC2-Pad9)") (class "Default")
      (node (ref "FPC2") (pin "9") (pinfunction "9_9") (pintype "unspecified+no_connect"))
    )
    (net (code "66") (name "unconnected-(FPC2-Pad10)") (class "Default")
      (node (ref "FPC2") (pin "10") (pinfunction "10_10") (pintype "unspecified+no_connect"))
    )
    (net (code "67") (name "unconnected-(SW1-Pad3)") (class "Default")
      (node (ref "SW1") (pin "3") (pinfunction "3_3") (pintype "unspecified+no_connect"))
    )
    (net (code "68") (name "unconnected-(SW1-Pad4)") (class "Default")
      (node (ref "SW1") (pin "4") (pinfunction "4_4") (pintype "unspecified+no_connect"))
    )
    (net (code "69") (name "unconnected-(SW2-Pad3)") (class "Default")
      (node (ref "SW2") (pin "3") (pinfunction "3_3") (pintype "unspecified+no_connect"))
    )
    (net (code "70") (name "unconnected-(SW2-Pad4)") (class "Default")
      (node (ref "SW2") (pin "4") (pinfunction "4_4") (pintype "unspecified+no_connect"))
    )
    (net (code "71") (name "unconnected-(SW3-Pad3)") (class "Default")
      (node (ref "SW3") (pin "3") (pinfunction "3_3") (pintype "unspecified+no_connect"))
    )
    (net (code "72") (name "unconnected-(SW3-Pad4)") (class "Default")
      (node (ref "SW3") (pin "4") (pinfunction "4_4") (pintype "unspecified+no_connect"))
    )
    (net (code "73") (name "unconnected-(SW4-Pad2)") (class "Default")
      (node (ref "SW4") (pin "2") (pinfunction "2_2") (pintype "unspecified+no_connect"))
    )
    (net (code "74") (name "unconnected-(SW4-Pad4)") (class "Default")
      (node (ref "SW4") (pin "4") (pinfunction "4_4") (pintype "unspecified+no_connect"))
    )
    (net (code "75") (name "unconnected-(SW5-Pad2)") (class "Default")
      (node (ref "SW5") (pin "2") (pinfunction "2_2") (pintype "unspecified+no_connect"))
    )
    (net (code "76") (name "unconnected-(SW5-Pad4)") (class "Default")
      (node (ref "SW5") (pin "4") (pinfunction "4_4") (pintype "unspecified+no_connect"))
    )
    (net (code "77") (name "unconnected-(U2-NC-Pad6)") (class "Default")
      (node (ref "U2") (pin "6") (pinfunction "NC_6") (pintype "unspecified+no_connect"))
    )
    (net (code "78") (name "unconnected-(U2-NC-Pad9)") (class "Default")
      (node (ref "U2") (pin "9") (pinfunction "NC_9") (pintype "unspecified+no_connect"))
    )
    (net (code "79") (name "unconnected-(U5-CS-AUX-Pad10)") (class "Default")
      (node (ref "U5") (pin "10") (pinfunction "CS-AUX_10") (pintype "unspecified+no_connect"))
    )
    (net (code "80") (name "unconnected-(U5-SDO-SUX-Pad11)") (class "Default")
      (node (ref "U5") (pin "11") (pinfunction "SDO-SUX_11") (pintype "unspecified+no_connect"))
    )
    (net (code "81") (name "unconnected-(U10-EP1-Pad9)") (class "Default")
      (node (ref "U10") (pin "9") (pinfunction "EP1_9") (pintype "unspecified+no_connect"))
    )
    (net (code "82") (name "unconnected-(U10-EP2-Pad10)") (class "Default")
      (node (ref "U10") (pin "10") (pinfunction "EP2_10") (pintype "unspecified+no_connect"))
    )
    (net (code "83") (name "unconnected-(USB-SBU1-PadA8)") (class "Default")
      (node (ref "USB") (pin "A8") (pinfunction "SBU1_A8") (pintype "unspecified+no_connect"))
    )
    (net (code "84") (name "unconnected-(USB-SBU2-PadB8)") (class "Default")
      (node (ref "USB") (pin "B8") (pinfunction "SBU2_B8") (pintype "unspecified+no_connect"))
    )
    (net (code "85") (name "unconnected-(USB-SH-Pad0)") (class "Default")
      (node (ref "USB") (pin "0") (pinfunction "SH_0") (pintype "unspecified+no_connect"))
    )
    (net (code "86") (name "unconnected-(USB-SH-Pad1)") (class "Default")
      (node (ref "USB") (pin "1") (pinfunction "SH_1") (pintype "unspecified+no_connect"))
    )
    (net (code "87") (name "unconnected-(USB-SH-Pad2)") (class "Default")
      (node (ref "USB") (pin "2") (pinfunction "SH_2") (pintype "unspecified+no_connect"))
    )
    (net (code "88") (name "unconnected-(USB-SH-Pad3)") (class "Default")
      (node (ref "USB") (pin "3") (pinfunction "SH_3") (pintype "unspecified+no_connect"))
    )
  )
)
